# BidirectionalLevelShifting.net
KiCad netlist of a schematic drawn in Altium Designer
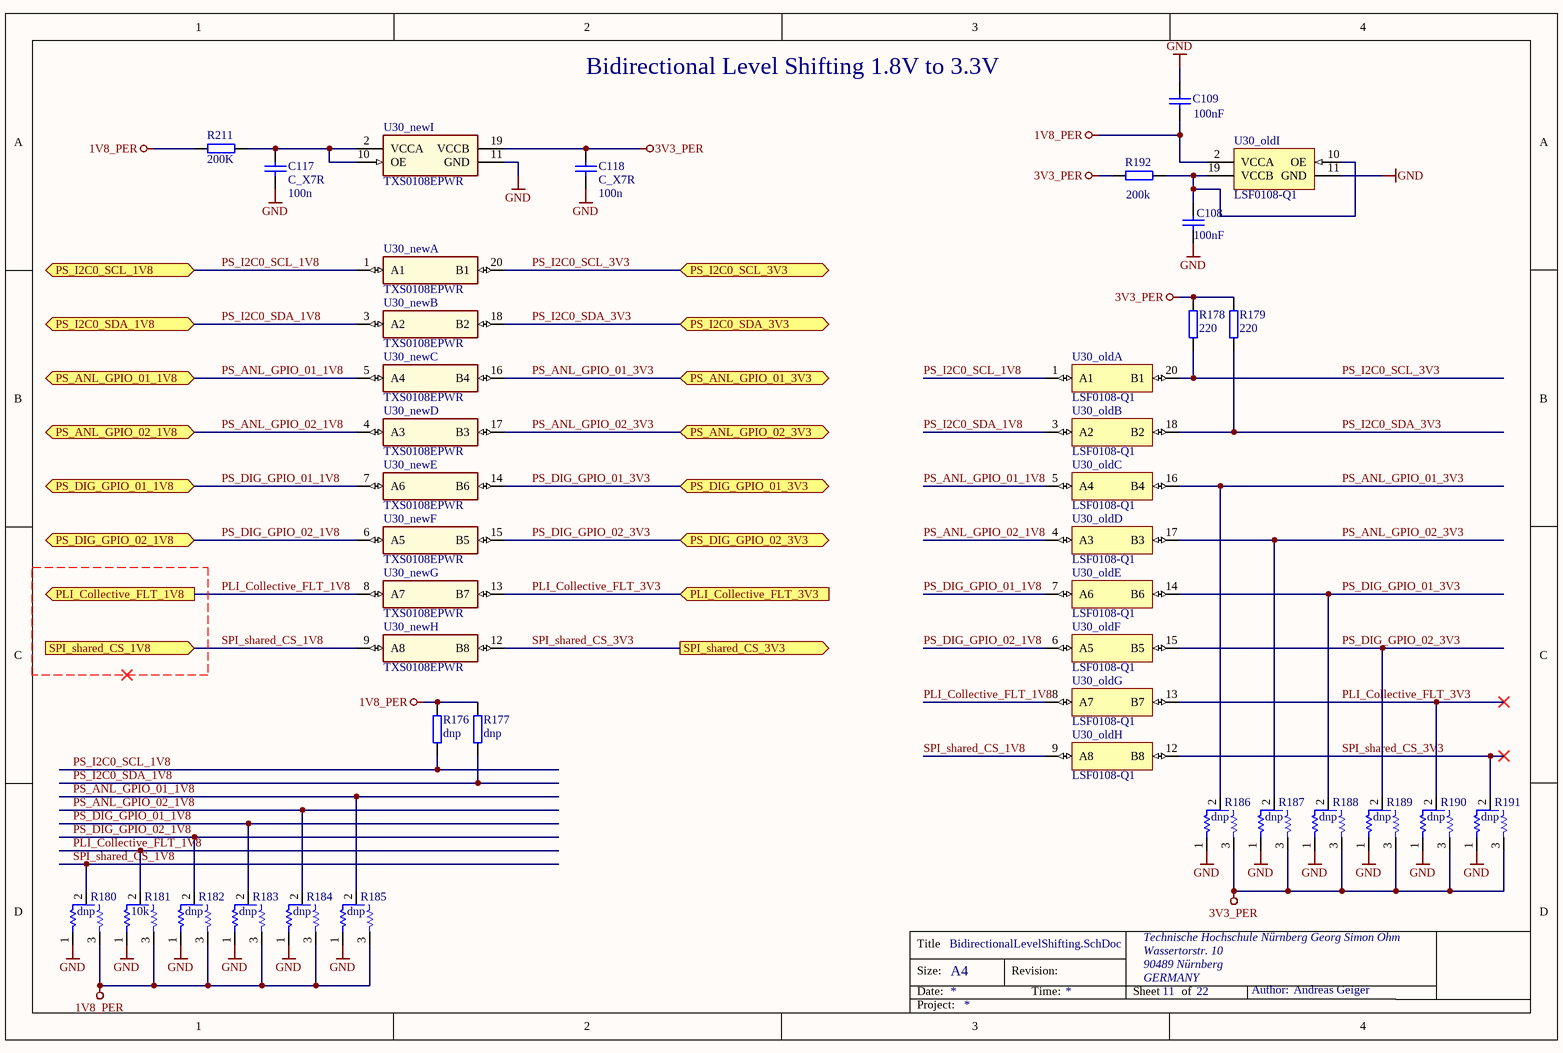
[diagram p0: BidirectionalLevelShifting.SchDoc]

(export (version "E")
  (design (tool "Eeschema 10.0.6"))
  (components
    (comp (ref "C108")
      (value "100nF")
      (footprint "C_0603(1608)100_L")
      (description "Capacitor 0603")
      (fields
        (field (name "TOLERANCE") "±10%")
        (field (name "VOLTAGE") "50V")
        (field (name "CREATED") "2018_09_13_AGeiger")
      )
      (libsource (lib "UltraZOhm_CarrierBoard") (part "C_0603"))
    )
    (comp (ref "C109")
      (value "100nF")
      (footprint "C_0603(1608)100_L")
      (description "Capacitor 0603")
      (fields
        (field (name "TOLERANCE") "±10%")
        (field (name "VOLTAGE") "50V")
        (field (name "CREATED") "2018_09_13_AGeiger")
      )
      (libsource (lib "UltraZOhm_CarrierBoard") (part "C_0603"))
    )
    (comp (ref "C117")
      (value "C_X7R")
      (footprint "CAPC_0603")
      (fields
        (field (name "MF") "KEMET")
        (field (name "MPN") "C<pkg[inch]><2d cap [pf] + #zeros><ToleranceSym><VoltageSym>RACTU")
        (field (name "ALTIUM_VALUE") "100n")
        (field (name "CREATED") "2019-12-08_Thilo_Wendt")
      )
      (libsource (lib "standard_rlc") (part "C_X7R_SMALL"))
    )
    (comp (ref "C118")
      (value "C_X7R")
      (footprint "CAPC_0603")
      (fields
        (field (name "MF") "KEMET")
        (field (name "MPN") "C<pkg[inch]><2d cap [pf] + #zeros><ToleranceSym><VoltageSym>RACTU")
        (field (name "ALTIUM_VALUE") "100n")
        (field (name "CREATED") "2019-12-08_Thilo_Wendt")
      )
      (libsource (lib "standard_rlc") (part "C_X7R_SMALL"))
    )
    (comp (ref "R176")
      (value "dnp")
      (footprint "R_0603_N")
      (description "SMD Resistor 0603")
      (fields
        (field (name "TOLERANCE") "1%")
        (field (name "VOLTAGE") "75V")
        (field (name "CREATED") "2018_09_06_AGeiger")
      )
      (libsource (lib "UltraZOhm_CarrierBoard") (part "R_0603"))
    )
    (comp (ref "R177")
      (value "dnp")
      (footprint "R_0603_N")
      (description "SMD Resistor 0603")
      (fields
        (field (name "TOLERANCE") "1%")
        (field (name "VOLTAGE") "75V")
        (field (name "CREATED") "2018_09_06_AGeiger")
      )
      (libsource (lib "UltraZOhm_CarrierBoard") (part "R_0603"))
    )
    (comp (ref "R178")
      (value "220")
      (footprint "R_0603_N")
      (description "SMD Resistor 0603")
      (fields
        (field (name "TOLERANCE") "1%")
        (field (name "VOLTAGE") "50V")
        (field (name "CREATED") "2019_10_12_AGeiger")
      )
      (libsource (lib "UltraZOhm_CarrierBoard") (part "R_0603"))
    )
    (comp (ref "R179")
      (value "220")
      (footprint "R_0603_N")
      (description "SMD Resistor 0603")
      (fields
        (field (name "TOLERANCE") "1%")
        (field (name "VOLTAGE") "50V")
        (field (name "CREATED") "2019_10_12_AGeiger")
      )
      (libsource (lib "UltraZOhm_CarrierBoard") (part "R_0603"))
    )
    (comp (ref "R180")
      (value "dnp")
      (footprint "0603_Config")
      (fields
        (field (name "MPN") "MCWR06X1002FTL")
        (field (name "MF") "Multicomp")
        (field (name "VOLTAGE") "50V")
        (field (name "CREATED") "2018_09_04_AGeiger")
      )
      (libsource (lib "UltraZOhm_CarrierBoard") (part "R_config"))
    )
    (comp (ref "R181")
      (value "10k")
      (footprint "0603_Config")
      (fields
        (field (name "MPN") "MCWR06X1002FTL")
        (field (name "MF") "Multicomp")
        (field (name "VOLTAGE") "50V")
        (field (name "CREATED") "2018_09_04_AGeiger")
      )
      (libsource (lib "UltraZOhm_CarrierBoard") (part "R_config"))
    )
    (comp (ref "R182")
      (value "dnp")
      (footprint "0603_Config")
      (fields
        (field (name "MPN") "MCWR06X1002FTL")
        (field (name "MF") "Multicomp")
        (field (name "VOLTAGE") "50V")
        (field (name "CREATED") "2018_09_04_AGeiger")
      )
      (libsource (lib "UltraZOhm_CarrierBoard") (part "R_config"))
    )
    (comp (ref "R183")
      (value "dnp")
      (footprint "0603_Config")
      (fields
        (field (name "MPN") "MCWR06X1002FTL")
        (field (name "MF") "Multicomp")
        (field (name "VOLTAGE") "50V")
        (field (name "CREATED") "2018_09_04_AGeiger")
      )
      (libsource (lib "UltraZOhm_CarrierBoard") (part "R_config"))
    )
    (comp (ref "R184")
      (value "dnp")
      (footprint "0603_Config")
      (fields
        (field (name "MPN") "MCWR06X1002FTL")
        (field (name "MF") "Multicomp")
        (field (name "VOLTAGE") "50V")
        (field (name "CREATED") "2018_09_04_AGeiger")
      )
      (libsource (lib "UltraZOhm_CarrierBoard") (part "R_config"))
    )
    (comp (ref "R185")
      (value "dnp")
      (footprint "0603_Config")
      (fields
        (field (name "MPN") "MCWR06X1002FTL")
        (field (name "MF") "Multicomp")
        (field (name "VOLTAGE") "50V")
        (field (name "CREATED") "2018_09_04_AGeiger")
      )
      (libsource (lib "UltraZOhm_CarrierBoard") (part "R_config"))
    )
    (comp (ref "R186")
      (value "dnp")
      (footprint "0603_Config")
      (fields
        (field (name "MPN") "MCWR06X1002FTL")
        (field (name "MF") "Multicomp")
        (field (name "VOLTAGE") "50V")
        (field (name "CREATED") "2018_09_04_AGeiger")
      )
      (libsource (lib "UltraZOhm_CarrierBoard") (part "R_config"))
    )
    (comp (ref "R187")
      (value "dnp")
      (footprint "0603_Config")
      (fields
        (field (name "MPN") "MCWR06X1002FTL")
        (field (name "MF") "Multicomp")
        (field (name "VOLTAGE") "50V")
        (field (name "CREATED") "2018_09_04_AGeiger")
      )
      (libsource (lib "UltraZOhm_CarrierBoard") (part "R_config"))
    )
    (comp (ref "R188")
      (value "dnp")
      (footprint "0603_Config")
      (fields
        (field (name "MPN") "MCWR06X1002FTL")
        (field (name "MF") "Multicomp")
        (field (name "VOLTAGE") "50V")
        (field (name "CREATED") "2018_09_04_AGeiger")
      )
      (libsource (lib "UltraZOhm_CarrierBoard") (part "R_config"))
    )
    (comp (ref "R189")
      (value "dnp")
      (footprint "0603_Config")
      (fields
        (field (name "MPN") "MCWR06X1002FTL")
        (field (name "MF") "Multicomp")
        (field (name "VOLTAGE") "50V")
        (field (name "CREATED") "2018_09_04_AGeiger")
      )
      (libsource (lib "UltraZOhm_CarrierBoard") (part "R_config"))
    )
    (comp (ref "R190")
      (value "dnp")
      (footprint "0603_Config")
      (fields
        (field (name "MPN") "MCWR06X1002FTL")
        (field (name "MF") "Multicomp")
        (field (name "VOLTAGE") "50V")
        (field (name "CREATED") "2018_09_04_AGeiger")
      )
      (libsource (lib "UltraZOhm_CarrierBoard") (part "R_config"))
    )
    (comp (ref "R191")
      (value "dnp")
      (footprint "0603_Config")
      (fields
        (field (name "MPN") "MCWR06X1002FTL")
        (field (name "MF") "Multicomp")
        (field (name "VOLTAGE") "50V")
        (field (name "CREATED") "2018_09_04_AGeiger")
      )
      (libsource (lib "UltraZOhm_CarrierBoard") (part "R_config"))
    )
    (comp (ref "R192")
      (value "200k")
      (footprint "R_0603_N")
      (description "SMD Resistor 0603")
      (fields
        (field (name "TOLERANCE") "1%")
        (field (name "VOLTAGE") "50V")
        (field (name "CREATED") "2018_09_06_AGeiger")
      )
      (libsource (lib "UltraZOhm_CarrierBoard") (part "R_0603"))
    )
    (comp (ref "R211")
      (value "200K")
      (footprint "R_0603_N")
      (description "SMD Resistor 0603")
      (fields
        (field (name "TOLERANCE") "1%")
        (field (name "VOLTAGE") "tbd")
        (field (name "CREATED") "2018_09_06_AGeiger")
      )
      (libsource (lib "UltraZOhm_CarrierBoard") (part "R_0603"))
    )
    (comp (ref "U30_new")
      (value "TXS0108EPWR")
      (footprint "TI_PW_R-PDSO-G20_L")
      (description "Integrated Circuit")
      (fields
        (field (name "MF") "Texas Instruments")
        (field (name "MPN") "TXS0108EQPWRQ1")
        (field (name "CREATED") "2020-05-05_Thilo_Wendt")
      )
      (libsource (lib "interface_ics") (part "TI-TXS0108EPWR"))
    )
    (comp (ref "U30_old")
      (value "LSF0108-Q1")
      (footprint "TI_PW_R-PDSO-G20_L")
      (description "Automotive 8-Channel Mulit-Voltage Level Translator")
      (fields
        (field (name "MF") "Texas Instruments")
        (field (name "MPN") "LSF0108QPWRQ1")
        (field (name "CREATED") "2018_09_17_AGeiger")
      )
      (libsource (lib "") (part "TI-LSF0108PWR_1"))
    )
  )
  (nets
    (net (code "1") (name "/PLI_Collective_FLT_1V8") (class "Default")
      (node (ref "R181") (pin "2") (pinfunction "2_2") (pintype "passive"))
      (node (ref "U30_new") (pin "8") (pinfunction "A7_8") (pintype "bidirectional"))
      (node (ref "U30_old") (pin "8") (pinfunction "A7_8") (pintype "bidirectional"))
    )
    (net (code "2") (name "/PLI_Collective_FLT_3V3") (class "Default")
      (node (ref "R190") (pin "2") (pinfunction "2_2") (pintype "passive"))
      (node (ref "U30_new") (pin "13") (pinfunction "B7_13") (pintype "bidirectional"))
      (node (ref "U30_old") (pin "13") (pinfunction "B7_13") (pintype "bidirectional"))
    )
    (net (code "3") (name "/PS_ANL_GPIO_01_1V8") (class "Default")
      (node (ref "R185") (pin "2") (pinfunction "2_2") (pintype "passive"))
      (node (ref "U30_new") (pin "5") (pinfunction "A4_5") (pintype "bidirectional"))
      (node (ref "U30_old") (pin "5") (pinfunction "A4_5") (pintype "bidirectional"))
    )
    (net (code "4") (name "/PS_ANL_GPIO_01_3V3") (class "Default")
      (node (ref "R186") (pin "2") (pinfunction "2_2") (pintype "passive"))
      (node (ref "U30_new") (pin "16") (pinfunction "B4_16") (pintype "bidirectional"))
      (node (ref "U30_old") (pin "16") (pinfunction "B4_16") (pintype "bidirectional"))
    )
    (net (code "5") (name "/PS_ANL_GPIO_02_1V8") (class "Default")
      (node (ref "R184") (pin "2") (pinfunction "2_2") (pintype "passive"))
      (node (ref "U30_new") (pin "4") (pinfunction "A3_4") (pintype "bidirectional"))
      (node (ref "U30_old") (pin "4") (pinfunction "A3_4") (pintype "bidirectional"))
    )
    (net (code "6") (name "/PS_ANL_GPIO_02_3V3") (class "Default")
      (node (ref "R187") (pin "2") (pinfunction "2_2") (pintype "passive"))
      (node (ref "U30_new") (pin "17") (pinfunction "B3_17") (pintype "bidirectional"))
      (node (ref "U30_old") (pin "17") (pinfunction "B3_17") (pintype "bidirectional"))
    )
    (net (code "7") (name "/PS_DIG_GPIO_01_1V8") (class "Default")
      (node (ref "R183") (pin "2") (pinfunction "2_2") (pintype "passive"))
      (node (ref "U30_new") (pin "7") (pinfunction "A6_7") (pintype "bidirectional"))
      (node (ref "U30_old") (pin "7") (pinfunction "A6_7") (pintype "bidirectional"))
    )
    (net (code "8") (name "/PS_DIG_GPIO_01_3V3") (class "Default")
      (node (ref "R188") (pin "2") (pinfunction "2_2") (pintype "passive"))
      (node (ref "U30_new") (pin "14") (pinfunction "B6_14") (pintype "bidirectional"))
      (node (ref "U30_old") (pin "14") (pinfunction "B6_14") (pintype "bidirectional"))
    )
    (net (code "9") (name "/PS_DIG_GPIO_02_1V8") (class "Default")
      (node (ref "R182") (pin "2") (pinfunction "2_2") (pintype "passive"))
      (node (ref "U30_new") (pin "6") (pinfunction "A5_6") (pintype "bidirectional"))
      (node (ref "U30_old") (pin "6") (pinfunction "A5_6") (pintype "bidirectional"))
    )
    (net (code "10") (name "/PS_DIG_GPIO_02_3V3") (class "Default")
      (node (ref "R189") (pin "2") (pinfunction "2_2") (pintype "passive"))
      (node (ref "U30_new") (pin "15") (pinfunction "B5_15") (pintype "bidirectional"))
      (node (ref "U30_old") (pin "15") (pinfunction "B5_15") (pintype "bidirectional"))
    )
    (net (code "11") (name "/PS_I2C0_SCL_1V8") (class "Default")
      (node (ref "R176") (pin "2") (pinfunction "2_2") (pintype "passive"))
      (node (ref "U30_new") (pin "1") (pinfunction "A1_1") (pintype "bidirectional"))
      (node (ref "U30_old") (pin "1") (pinfunction "A1_1") (pintype "bidirectional"))
    )
    (net (code "12") (name "/PS_I2C0_SCL_3V3") (class "Default")
      (node (ref "R178") (pin "2") (pinfunction "2_2") (pintype "passive"))
      (node (ref "U30_new") (pin "20") (pinfunction "B1_20") (pintype "bidirectional"))
      (node (ref "U30_old") (pin "20") (pinfunction "B1_20") (pintype "bidirectional"))
    )
    (net (code "13") (name "/PS_I2C0_SDA_1V8") (class "Default")
      (node (ref "R177") (pin "2") (pinfunction "2_2") (pintype "passive"))
      (node (ref "U30_new") (pin "3") (pinfunction "A2_3") (pintype "bidirectional"))
      (node (ref "U30_old") (pin "3") (pinfunction "A2_3") (pintype "bidirectional"))
    )
    (net (code "14") (name "/PS_I2C0_SDA_3V3") (class "Default")
      (node (ref "R179") (pin "2") (pinfunction "2_2") (pintype "passive"))
      (node (ref "U30_new") (pin "18") (pinfunction "B2_18") (pintype "bidirectional"))
      (node (ref "U30_old") (pin "18") (pinfunction "B2_18") (pintype "bidirectional"))
    )
    (net (code "15") (name "/SPI_shared_CS_1V8") (class "Default")
      (node (ref "R180") (pin "2") (pinfunction "2_2") (pintype "passive"))
      (node (ref "U30_new") (pin "9") (pinfunction "A8_9") (pintype "bidirectional"))
      (node (ref "U30_old") (pin "9") (pinfunction "A8_9") (pintype "bidirectional"))
    )
    (net (code "16") (name "/SPI_shared_CS_3V3") (class "Default")
      (node (ref "R191") (pin "2") (pinfunction "2_2") (pintype "passive"))
      (node (ref "U30_new") (pin "12") (pinfunction "B8_12") (pintype "bidirectional"))
      (node (ref "U30_old") (pin "12") (pinfunction "B8_12") (pintype "bidirectional"))
    )
    (net (code "17") (name "1V8_PER") (class "Default")
      (node (ref "C109") (pin "2") (pinfunction "2_2") (pintype "passive"))
      (node (ref "R176") (pin "1") (pinfunction "1_1") (pintype "passive"))
      (node (ref "R177") (pin "1") (pinfunction "1_1") (pintype "passive"))
      (node (ref "R180") (pin "3") (pinfunction "3_3") (pintype "passive"))
      (node (ref "R181") (pin "3") (pinfunction "3_3") (pintype "passive"))
      (node (ref "R182") (pin "3") (pinfunction "3_3") (pintype "passive"))
      (node (ref "R183") (pin "3") (pinfunction "3_3") (pintype "passive"))
      (node (ref "R184") (pin "3") (pinfunction "3_3") (pintype "passive"))
      (node (ref "R185") (pin "3") (pinfunction "3_3") (pintype "passive"))
      (node (ref "R211") (pin "1") (pinfunction "1_1") (pintype "passive"))
      (node (ref "U30_old") (pin "2") (pinfunction "VCCA_2") (pintype "power_in"))
    )
    (net (code "18") (name "3V3_PER") (class "Default")
      (node (ref "C118") (pin "2") (pinfunction "2_2") (pintype "passive"))
      (node (ref "R178") (pin "1") (pinfunction "1_1") (pintype "passive"))
      (node (ref "R179") (pin "1") (pinfunction "1_1") (pintype "passive"))
      (node (ref "R186") (pin "3") (pinfunction "3_3") (pintype "passive"))
      (node (ref "R187") (pin "3") (pinfunction "3_3") (pintype "passive"))
      (node (ref "R188") (pin "3") (pinfunction "3_3") (pintype "passive"))
      (node (ref "R189") (pin "3") (pinfunction "3_3") (pintype "passive"))
      (node (ref "R190") (pin "3") (pinfunction "3_3") (pintype "passive"))
      (node (ref "R191") (pin "3") (pinfunction "3_3") (pintype "passive"))
      (node (ref "R192") (pin "2") (pinfunction "2_2") (pintype "passive"))
      (node (ref "U30_new") (pin "19") (pinfunction "VCCB_19") (pintype "power_in"))
    )
    (net (code "19") (name "GND") (class "Default")
      (node (ref "C108") (pin "1") (pinfunction "1_1") (pintype "passive"))
      (node (ref "C109") (pin "1") (pinfunction "1_1") (pintype "passive"))
      (node (ref "C117") (pin "1") (pinfunction "1_1") (pintype "passive"))
      (node (ref "C118") (pin "1") (pinfunction "1_1") (pintype "passive"))
      (node (ref "R180") (pin "1") (pinfunction "1_1") (pintype "passive"))
      (node (ref "R181") (pin "1") (pinfunction "1_1") (pintype "passive"))
      (node (ref "R182") (pin "1") (pinfunction "1_1") (pintype "passive"))
      (node (ref "R183") (pin "1") (pinfunction "1_1") (pintype "passive"))
      (node (ref "R184") (pin "1") (pinfunction "1_1") (pintype "passive"))
      (node (ref "R185") (pin "1") (pinfunction "1_1") (pintype "passive"))
      (node (ref "R186") (pin "1") (pinfunction "1_1") (pintype "passive"))
      (node (ref "R187") (pin "1") (pinfunction "1_1") (pintype "passive"))
      (node (ref "R188") (pin "1") (pinfunction "1_1") (pintype "passive"))
      (node (ref "R189") (pin "1") (pinfunction "1_1") (pintype "passive"))
      (node (ref "R190") (pin "1") (pinfunction "1_1") (pintype "passive"))
      (node (ref "R191") (pin "1") (pinfunction "1_1") (pintype "passive"))
      (node (ref "U30_new") (pin "11") (pinfunction "GND_11") (pintype "power_in"))
      (node (ref "U30_old") (pin "11") (pinfunction "GND_11") (pintype "power_in"))
    )
    (net (code "20") (name "Net-(U30_newI-OE)") (class "Default")
      (node (ref "C117") (pin "2") (pinfunction "2_2") (pintype "passive"))
      (node (ref "R211") (pin "2") (pinfunction "2_2") (pintype "passive"))
      (node (ref "U30_new") (pin "10") (pinfunction "OE_10") (pintype "input"))
      (node (ref "U30_new") (pin "2") (pinfunction "VCCA_2") (pintype "power_in"))
    )
    (net (code "21") (name "Net-(U30_oldI-OE)") (class "Default")
      (node (ref "C108") (pin "2") (pinfunction "2_2") (pintype "passive"))
      (node (ref "R192") (pin "1") (pinfunction "1_1") (pintype "passive"))
      (node (ref "U30_old") (pin "10") (pinfunction "OE_10") (pintype "input"))
      (node (ref "U30_old") (pin "19") (pinfunction "VCCB_19") (pintype "power_in"))
    )
  )
)
